# 5_Flash_SDCard.net
KiCad netlist of a schematic drawn in Altium Designer
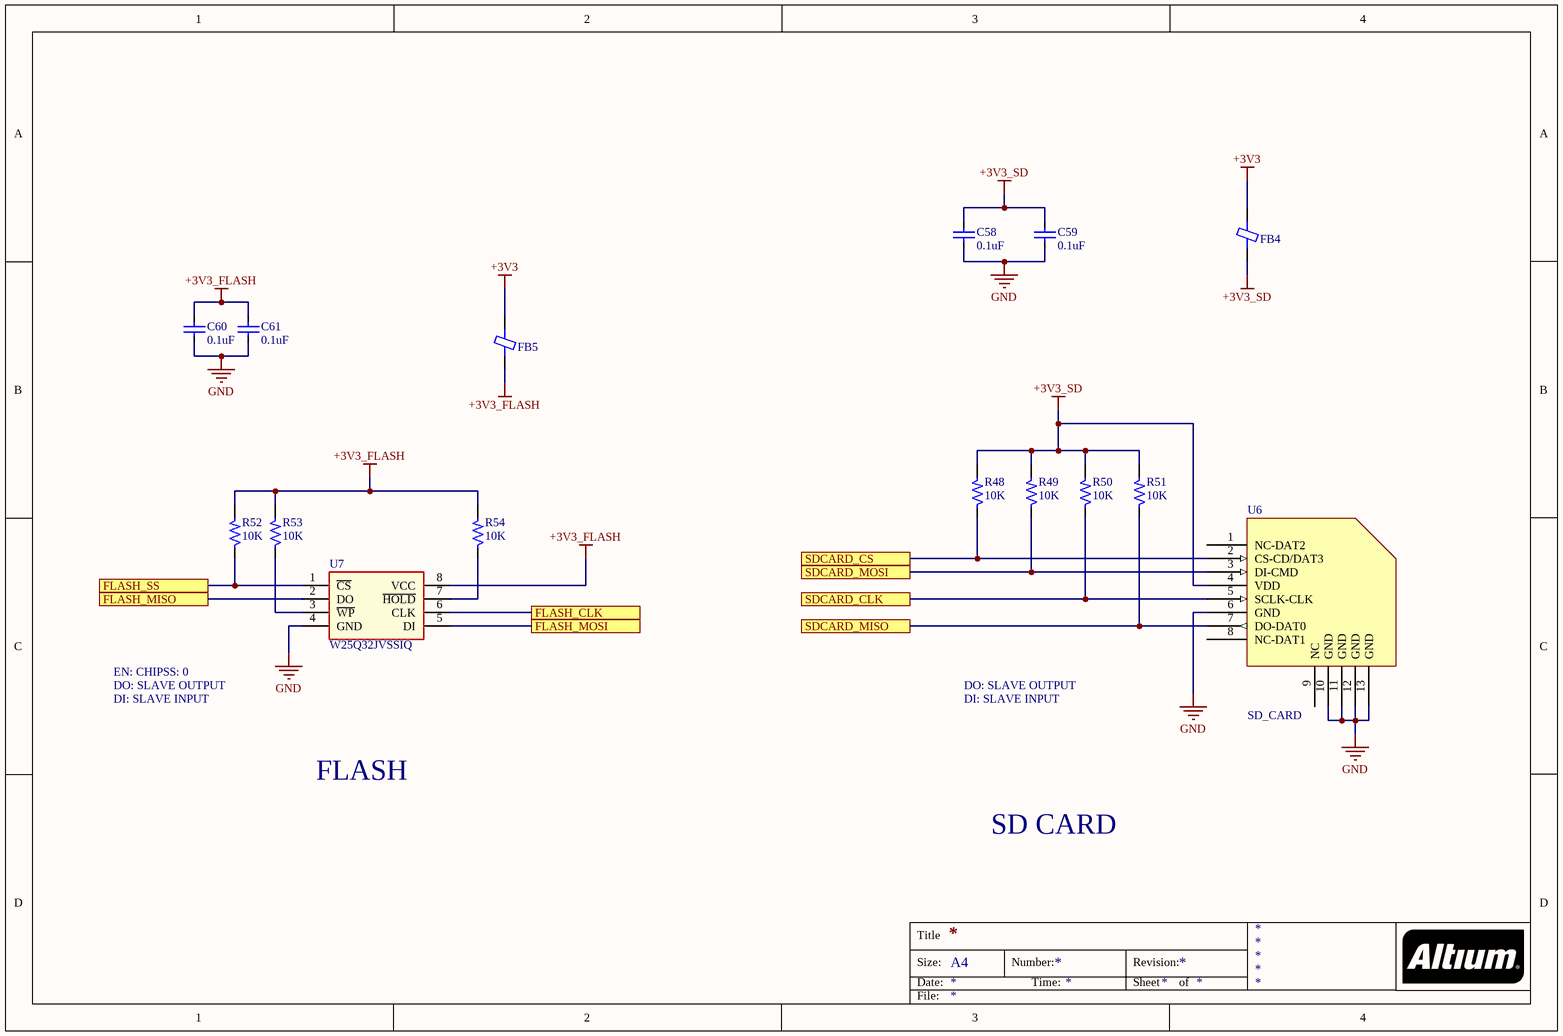
[diagram p0: [5]Flash_SDCard.SchDoc]

(export (version "E")
  (design (tool "Eeschema 10.0.6"))
  (components
    (comp (ref "C58")
      (value "0.1uF")
      (footprint "CAP_0805")
      (description "Capacitor")
      (fields (field (name "PUBLISHER") "Altium Limited"))
      (libsource (lib "My Library") (part "CapSMD"))
    )
    (comp (ref "C59")
      (value "0.1uF")
      (footprint "CAP_0805")
      (description "Capacitor")
      (fields (field (name "PUBLISHER") "Altium Limited"))
      (libsource (lib "My Library") (part "CapSMD"))
    )
    (comp (ref "C60")
      (value "0.1uF")
      (footprint "CAP_0805")
      (description "Capacitor")
      (fields (field (name "PUBLISHER") "Altium Limited"))
      (libsource (lib "My Library") (part "CapSMD"))
    )
    (comp (ref "C61")
      (value "0.1uF")
      (footprint "CAP_0805")
      (description "Capacitor")
      (fields (field (name "PUBLISHER") "Altium Limited"))
      (libsource (lib "My Library") (part "CapSMD"))
    )
    (comp (ref "FB4")
      (value "120R")
      (footprint "RES-SMD-0805")
      (description "Ferrite beads")
      (libsource (lib "bla") (part "Ferrite beads"))
    )
    (comp (ref "FB5")
      (value "120R")
      (footprint "RES-SMD-0805")
      (description "Ferrite beads")
      (libsource (lib "bla") (part "Ferrite beads"))
    )
    (comp (ref "R48")
      (value "10K")
      (footprint "R0805")
      (description "Resistor SMD")
      (libsource (lib "GPS_Traking_V1_1") (part "RM"))
    )
    (comp (ref "R49")
      (value "10K")
      (footprint "R0805")
      (description "Resistor SMD")
      (libsource (lib "GPS_Traking_V1_1") (part "RM"))
    )
    (comp (ref "R50")
      (value "10K")
      (footprint "R0805")
      (description "Resistor SMD")
      (libsource (lib "GPS_Traking_V1_1") (part "RM"))
    )
    (comp (ref "R51")
      (value "10K")
      (footprint "R0805")
      (description "Resistor SMD")
      (libsource (lib "GPS_Traking_V1_1") (part "RM"))
    )
    (comp (ref "R52")
      (value "10K")
      (footprint "R0805")
      (description "Resistor SMD")
      (libsource (lib "GPS_Traking_V1_1") (part "RM"))
    )
    (comp (ref "R53")
      (value "10K")
      (footprint "R0805")
      (description "Resistor SMD")
      (libsource (lib "GPS_Traking_V1_1") (part "RM"))
    )
    (comp (ref "R54")
      (value "10K")
      (footprint "R0805")
      (description "Resistor SMD")
      (libsource (lib "GPS_Traking_V1_1") (part "RM"))
    )
    (comp (ref "U6")
      (value "SD_CARD")
      (footprint "MICROSD2")
      (description "SD/MMC holder")
      (libsource (lib "Anh_Trung") (part "MicroSD"))
    )
    (comp (ref "U7")
      (value "W25Q32JVSSIQ")
      (footprint "SO-8 208")
      (description "FLASH 32MBIT 133MHZ 8SOP")
      (libsource (lib "GPS_Traking_V1_1") (part "W25Q32JV"))
    )
  )
  (nets
    (net (code "1") (name "+3V3") (class "Default")
      (node (ref "FB4") (pin "1") (pinfunction "1_1") (pintype "passive"))
      (node (ref "FB5") (pin "1") (pinfunction "1_1") (pintype "passive"))
    )
    (net (code "2") (name "+3V3_FLASH") (class "Default")
      (node (ref "C60") (pin "2") (pinfunction "2_2") (pintype "passive"))
      (node (ref "C61") (pin "2") (pinfunction "2_2") (pintype "passive"))
      (node (ref "FB5") (pin "2") (pinfunction "2_2") (pintype "passive"))
      (node (ref "R52") (pin "2") (pinfunction "2_2") (pintype "passive"))
      (node (ref "R53") (pin "2") (pinfunction "2_2") (pintype "passive"))
      (node (ref "R54") (pin "2") (pinfunction "2_2") (pintype "passive"))
      (node (ref "U7") (pin "8") (pinfunction "VCC_8") (pintype "passive"))
    )
    (net (code "3") (name "+3V3_SD") (class "Default")
      (node (ref "C58") (pin "2") (pinfunction "2_2") (pintype "passive"))
      (node (ref "C59") (pin "2") (pinfunction "2_2") (pintype "passive"))
      (node (ref "FB4") (pin "2") (pinfunction "2_2") (pintype "passive"))
      (node (ref "R48") (pin "2") (pinfunction "2_2") (pintype "passive"))
      (node (ref "R49") (pin "2") (pinfunction "2_2") (pintype "passive"))
      (node (ref "R50") (pin "2") (pinfunction "2_2") (pintype "passive"))
      (node (ref "R51") (pin "2") (pinfunction "2_2") (pintype "passive"))
      (node (ref "U6") (pin "4") (pinfunction "VDD_4") (pintype "passive"))
    )
    (net (code "4") (name "/FLASH_CLK") (class "Default")
      (node (ref "U7") (pin "6") (pinfunction "CLK_6") (pintype "passive"))
    )
    (net (code "5") (name "/FLASH_MISO") (class "Default")
      (node (ref "U7") (pin "2") (pinfunction "DO_2") (pintype "passive"))
    )
    (net (code "6") (name "/FLASH_MOSI") (class "Default")
      (node (ref "U7") (pin "5") (pinfunction "DI_5") (pintype "passive"))
    )
    (net (code "7") (name "/FLASH_SS") (class "Default")
      (node (ref "R52") (pin "1") (pinfunction "1_1") (pintype "passive"))
      (node (ref "U7") (pin "1") (pinfunction "~{CS}_1") (pintype "passive"))
    )
    (net (code "8") (name "/SDCARD_CLK") (class "Default")
      (node (ref "R50") (pin "1") (pinfunction "1_1") (pintype "passive"))
      (node (ref "U6") (pin "5") (pinfunction "SCLK-CLK_5") (pintype "input"))
    )
    (net (code "9") (name "/SDCARD_CS") (class "Default")
      (node (ref "R48") (pin "1") (pinfunction "1_1") (pintype "passive"))
      (node (ref "U6") (pin "2") (pinfunction "CS-CD/DAT3_2") (pintype "input"))
    )
    (net (code "10") (name "/SDCARD_MISO") (class "Default")
      (node (ref "R51") (pin "1") (pinfunction "1_1") (pintype "passive"))
      (node (ref "U6") (pin "7") (pinfunction "DO-DAT0_7") (pintype "output"))
    )
    (net (code "11") (name "/SDCARD_MOSI") (class "Default")
      (node (ref "R49") (pin "1") (pinfunction "1_1") (pintype "passive"))
      (node (ref "U6") (pin "3") (pinfunction "DI-CMD_3") (pintype "input"))
    )
    (net (code "12") (name "GND") (class "Default")
      (node (ref "C58") (pin "1") (pinfunction "1_1") (pintype "passive"))
      (node (ref "C59") (pin "1") (pinfunction "1_1") (pintype "passive"))
      (node (ref "C60") (pin "1") (pinfunction "1_1") (pintype "passive"))
      (node (ref "C61") (pin "1") (pinfunction "1_1") (pintype "passive"))
      (node (ref "U6") (pin "10") (pinfunction "GND_10") (pintype "passive"))
      (node (ref "U6") (pin "11") (pinfunction "GND_11") (pintype "passive"))
      (node (ref "U6") (pin "12") (pinfunction "GND_12") (pintype "passive"))
      (node (ref "U6") (pin "13") (pinfunction "GND_13") (pintype "passive"))
      (node (ref "U6") (pin "6") (pinfunction "GND_6") (pintype "passive"))
      (node (ref "U7") (pin "4") (pinfunction "GND_4") (pintype "passive"))
    )
    (net (code "13") (name "Net-(U7-~{HOLD})") (class "Default")
      (node (ref "R54") (pin "1") (pinfunction "1_1") (pintype "passive"))
      (node (ref "U7") (pin "7") (pinfunction "~{HOLD}_7") (pintype "passive"))
    )
    (net (code "14") (name "Net-(U7-~{WP})") (class "Default")
      (node (ref "R53") (pin "1") (pinfunction "1_1") (pintype "passive"))
      (node (ref "U7") (pin "3") (pinfunction "~{WP}_3") (pintype "passive"))
    )
    (net (code "15") (name "unconnected-(U6-NC-DAT1-Pad8)") (class "Default")
      (node (ref "U6") (pin "8") (pinfunction "NC-DAT1_8") (pintype "passive"))
    )
    (net (code "16") (name "unconnected-(U6-NC-DAT2-Pad1)") (class "Default")
      (node (ref "U6") (pin "1") (pinfunction "NC-DAT2_1") (pintype "passive"))
    )
    (net (code "17") (name "unconnected-(U6-NC-Pad9)") (class "Default")
      (node (ref "U6") (pin "9") (pinfunction "NC_9") (pintype "passive"))
    )
  )
)
